# untitled.net
KiCad netlist of a schematic drawn in EAGLE
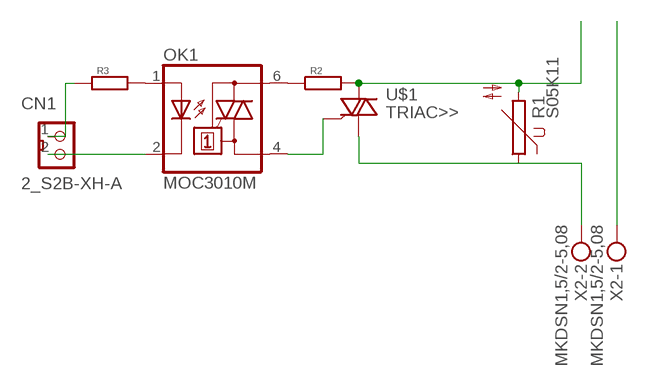
[diagram p0: schematic, sheet 1]

(export (version "E")
  (design (tool "Eeschema 10.0.6"))
  (components
    (comp (ref "CN1")
      (value "2_S2B-XH-A")
      (footprint "eagle-import:S2B-XH-A")
      (libsource (lib "eagle-import") (part "2_S2B-XH-A"))
    )
    (comp (ref "OK1")
      (value "MOC3010M")
      (footprint "eagle-import:DIL06")
      (fields (field (name "MF") "FAIRCHILD SEMICONDUCTOR") (field (name "MPN") "MOC3010-M"))
      (libsource (lib "eagle-import") (part "MOC30M10"))
    )
    (comp (ref "R1")
      (value "S05K11")
      (footprint "eagle-import:S05K11")
      (libsource (lib "eagle-import") (part "S05K11"))
    )
    (comp (ref "R2")
      (value "R-EU>>1/4W(8MM)")
      (footprint "eagle-import:1_4W(8MM)")
      (libsource (lib "eagle-import") (part "R-EU{gt}{gt}1/4W(8MM)"))
    )
    (comp (ref "R3")
      (value "R-EU>>1/4W(8MM)")
      (footprint "eagle-import:1_4W(8MM)")
      (libsource (lib "eagle-import") (part "R-EU{gt}{gt}1/4W(8MM)"))
    )
    (comp (ref "U$1")
      (value "TRIAC>>")
      (footprint "eagle-import:TO-220_BT")
      (libsource (lib "eagle-import") (part "TRIAC{gt}{gt}"))
    )
    (comp (ref "X2")
      (value "MKDSN1,5/2-5,08")
      (footprint "eagle-import:MKDSN1,5_2-5,08")
      (fields (field (name "MPN") "MKDSN 1,5/2-5.08"))
      (libsource (lib "eagle-import") (part "MKDSN1,5/2-5,08"))
    )
  )
  (nets
    (net (code "1") (name "Net-(CN1-Pad1)") (class "Default")
      (node (ref "CN1") (pin "1") (pinfunction "1_1") (pintype "passive"))
      (node (ref "R3") (pin "1") (pinfunction "1_1") (pintype "passive"))
    )
    (net (code "2") (name "Net-(OK1-A)") (class "Default")
      (node (ref "OK1") (pin "1") (pinfunction "A_1") (pintype "passive"))
      (node (ref "R3") (pin "2") (pinfunction "2_2") (pintype "passive"))
    )
    (net (code "3") (name "Net-(OK1-A1)") (class "Default")
      (node (ref "OK1") (pin "4") (pinfunction "A1_4") (pintype "passive"))
      (node (ref "U$1") (pin "1") (pinfunction "G_1") (pintype "passive"))
    )
    (net (code "4") (name "Net-(OK1-A2)") (class "Default")
      (node (ref "OK1") (pin "6") (pinfunction "A2_6") (pintype "passive"))
      (node (ref "R2") (pin "1") (pinfunction "1_1") (pintype "passive"))
    )
    (net (code "5") (name "Net-(OK1-C)") (class "Default")
      (node (ref "CN1") (pin "2") (pinfunction "2_2") (pintype "passive"))
      (node (ref "OK1") (pin "2") (pinfunction "C_2") (pintype "passive"))
    )
    (net (code "6") (name "Net-(U$1-A1)") (class "Default")
      (node (ref "R1") (pin "1") (pinfunction "1_1") (pintype "passive"))
      (node (ref "U$1") (pin "3") (pinfunction "A1_3") (pintype "passive"))
      (node (ref "X2") (pin "2") (pinfunction "KL_2") (pintype "passive"))
    )
    (net (code "7") (name "Net-(U$1-A2)") (class "Default")
      (node (ref "R1") (pin "2") (pinfunction "2_2") (pintype "passive"))
      (node (ref "R2") (pin "2") (pinfunction "2_2") (pintype "passive"))
      (node (ref "U$1") (pin "2") (pinfunction "A2_2") (pintype "passive"))
    )
    (net (code "8") (name "unconnected-(X2A-KL-Pad1)") (class "Default")
      (node (ref "X2") (pin "1") (pinfunction "KL_1") (pintype "passive"))
    )
  )
)
